# encoder-filter-diagram.net
KiCad netlist of a schematic drawn in Altium Designer
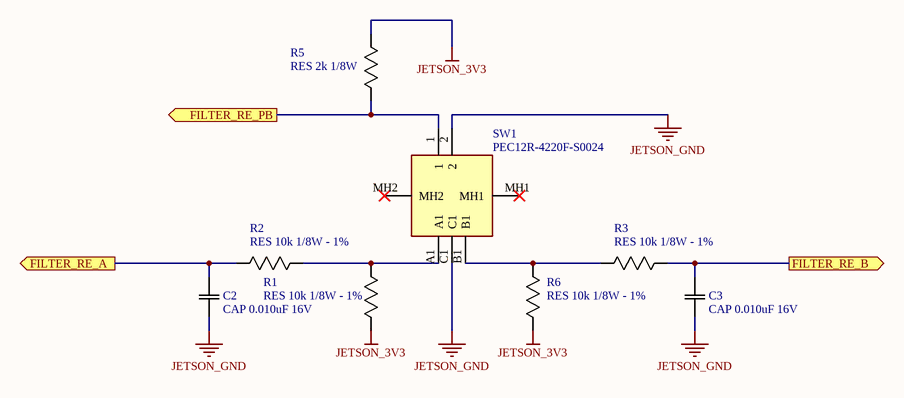
[diagram p0: encoder-filter-diagram.SchDoc]

(export (version "E")
  (design (tool "Eeschema 10.0.6"))
  (components
    (comp (ref "C2")
      (value "CAP 0.010uF 16V")
      (footprint "0603")
      (description "Default Symbol for Capacitors")
      (fields (field (name "TOLERANCE") "10%"))
      (libsource (lib "capacitor_library") (part "CAP_Default"))
    )
    (comp (ref "C3")
      (value "CAP 0.010uF 16V")
      (footprint "0603")
      (description "Default Symbol for Capacitors")
      (fields (field (name "TOLERANCE") "10%"))
      (libsource (lib "capacitor_library") (part "CAP_Default"))
    )
    (comp (ref "R1")
      (value "RES 10k 1/8W - 1%")
      (footprint "0603")
      (description "Default Resistor Symbol")
      (fields (field (name "TOLERANCE") "5%"))
      (libsource (lib "") (part "RES_DEFAULT_1"))
    )
    (comp (ref "R2")
      (value "RES 10k 1/8W - 1%")
      (footprint "0603")
      (description "Default Resistor Symbol")
      (fields (field (name "TOLERANCE") "5%"))
      (libsource (lib "Resistor_Library") (part "RES_DEFAULT"))
    )
    (comp (ref "R3")
      (value "RES 10k 1/8W - 1%")
      (footprint "0603")
      (description "Default Resistor Symbol")
      (fields (field (name "TOLERANCE") "5%"))
      (libsource (lib "") (part "RES_DEFAULT_1"))
    )
    (comp (ref "R5")
      (value "RES 2k 1/8W")
      (footprint "0603")
      (description "Default Resistor Symbol")
      (fields (field (name "TOLERANCE") "5%"))
      (libsource (lib "Resistor_Library") (part "RES_DEFAULT"))
    )
    (comp (ref "R6")
      (value "RES 10k 1/8W - 1%")
      (footprint "0603")
      (description "Default Resistor Symbol")
      (fields (field (name "TOLERANCE") "5%"))
      (libsource (lib "Resistor_Library") (part "RES_DEFAULT"))
    )
    (comp (ref "SW1")
      (value "PEC12R-4220F-S0024")
      (footprint "PEC12R4220FS0024")
      (description "Rotary Encoder")
      (fields
        (field (name "MOUSER PART NUMBER") "652-PEC12R-4220F-S24")
        (field (name "PART NUMBER") "PEC12R4220FS0024")
      )
      (libsource (lib "Switch_Library") (part "PEC12R-4220F-S0024"))
    )
  )
  (nets
    (net (code "1") (name "/FILTER_RE_A") (class "Default")
      (node (ref "C2") (pin "2") (pinfunction "C2_2") (pintype "passive"))
      (node (ref "R2") (pin "2") (pinfunction "R2_2") (pintype "passive"))
    )
    (net (code "2") (name "/FILTER_RE_B") (class "Default")
      (node (ref "C3") (pin "2") (pinfunction "C2_2") (pintype "passive"))
      (node (ref "R3") (pin "1") (pinfunction "R1_1") (pintype "passive"))
    )
    (net (code "3") (name "/FILTER_RE_PB") (class "Default")
      (node (ref "R5") (pin "2") (pinfunction "R2_2") (pintype "passive"))
      (node (ref "SW1") (pin "1") (pinfunction "1_1") (pintype "passive"))
    )
    (net (code "4") (name "JETSON_3V3") (class "Default")
      (node (ref "R1") (pin "2") (pinfunction "R2_2") (pintype "passive"))
      (node (ref "R5") (pin "1") (pinfunction "R1_1") (pintype "passive"))
      (node (ref "R6") (pin "2") (pinfunction "R2_2") (pintype "passive"))
    )
    (net (code "5") (name "JETSON_GND") (class "Default")
      (node (ref "C2") (pin "1") (pinfunction "C1_1") (pintype "passive"))
      (node (ref "C3") (pin "1") (pinfunction "C1_1") (pintype "passive"))
      (node (ref "SW1") (pin "2") (pinfunction "2_2") (pintype "passive"))
      (node (ref "SW1") (pin "C1") (pinfunction "C1_C1") (pintype "passive"))
    )
    (net (code "6") (name "Net-(R1-R1)") (class "Default")
      (node (ref "R1") (pin "1") (pinfunction "R1_1") (pintype "passive"))
      (node (ref "R2") (pin "1") (pinfunction "R1_1") (pintype "passive"))
      (node (ref "SW1") (pin "A1") (pinfunction "A1_A1") (pintype "passive"))
    )
    (net (code "7") (name "Net-(R3-R2)") (class "Default")
      (node (ref "R3") (pin "2") (pinfunction "R2_2") (pintype "passive"))
      (node (ref "R6") (pin "1") (pinfunction "R1_1") (pintype "passive"))
      (node (ref "SW1") (pin "B1") (pinfunction "B1_B1") (pintype "passive"))
    )
    (net (code "8") (name "unconnected-(SW1-PadMH1)") (class "Default")
      (node (ref "SW1") (pin "MH1") (pinfunction "MH1_MH1") (pintype "passive+no_connect"))
    )
    (net (code "9") (name "unconnected-(SW1-PadMH2)") (class "Default")
      (node (ref "SW1") (pin "MH2") (pinfunction "MH2_MH2") (pintype "passive+no_connect"))
    )
  )
)
